# ITG-3200-v11.net
KiCad netlist of a schematic drawn in EAGLE
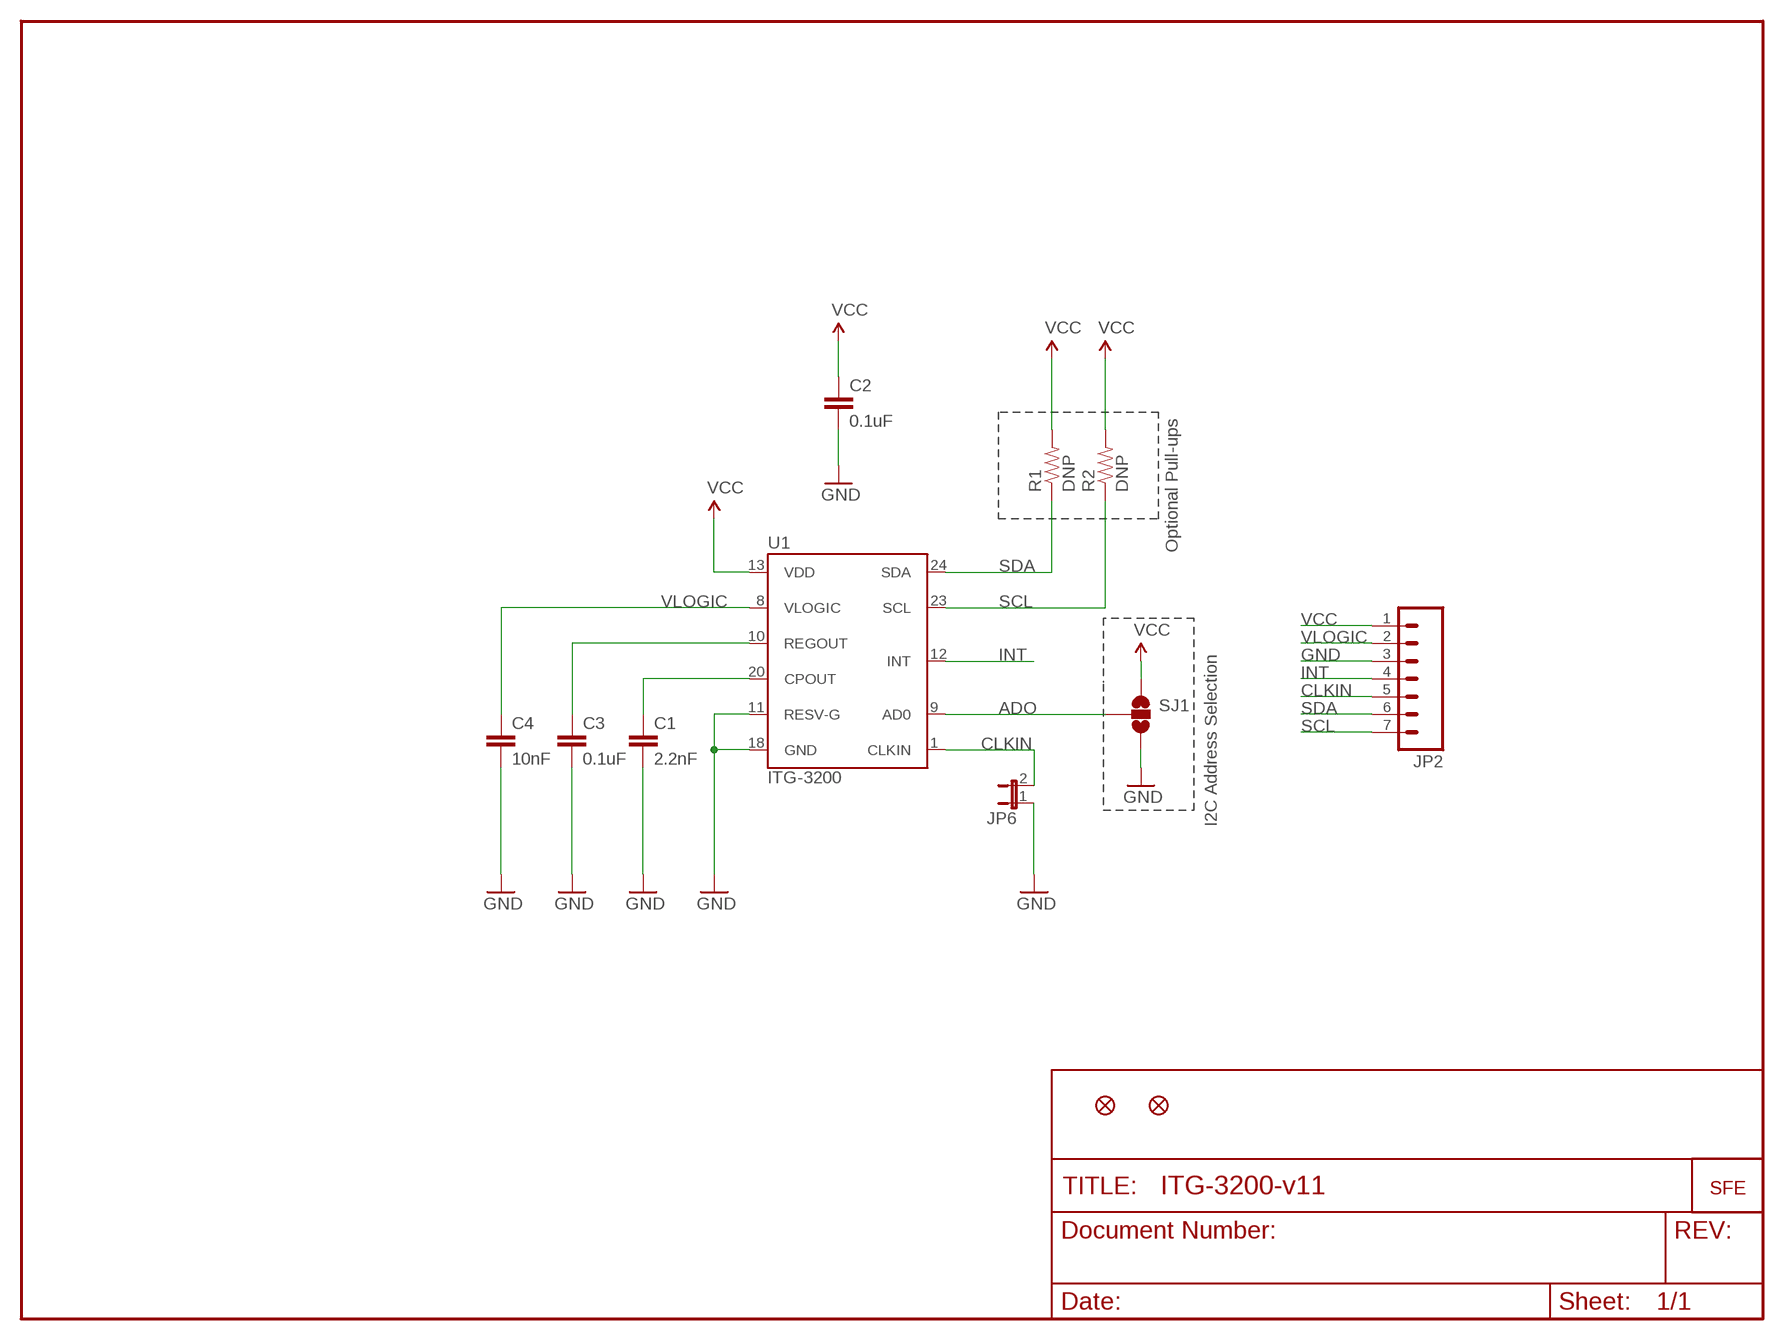
[diagram p0: schematic, sheet 1]

(export (version "E")
  (design (tool "Eeschema 10.0.6"))
  (components
    (comp (ref "C1")
      (value "2.2nF")
      (footprint "eagle-import:0603-CAP")
      (libsource (lib "eagle-import") (part "CAP0603-CAP"))
    )
    (comp (ref "C2")
      (value "0.1uF")
      (footprint "eagle-import:0603-CAP")
      (libsource (lib "eagle-import") (part "CAP0603-CAP"))
    )
    (comp (ref "C3")
      (value "0.1uF")
      (footprint "eagle-import:0603-CAP")
      (libsource (lib "eagle-import") (part "CAP0603-CAP"))
    )
    (comp (ref "C4")
      (value "10nF")
      (footprint "eagle-import:0603-CAP")
      (libsource (lib "eagle-import") (part "CAP0603-CAP"))
    )
    (comp (ref "JP1")
      (value "LOGO-SFESK")
      (footprint "eagle-import:SFE-LOGO-FLAME")
      (libsource (lib "eagle-import") (part "LOGO-SFESK"))
    )
    (comp (ref "JP2")
      (value "M07")
      (footprint "eagle-import:1X07")
      (libsource (lib "eagle-import") (part "M07"))
    )
    (comp (ref "JP3")
      (value "FIDUCIAL1X2")
      (footprint "eagle-import:FIDUCIAL-1X2")
      (libsource (lib "eagle-import") (part "FIDUCIAL1X2"))
    )
    (comp (ref "JP4")
      (value "FIDUCIAL1X2")
      (footprint "eagle-import:FIDUCIAL-1X2")
      (libsource (lib "eagle-import") (part "FIDUCIAL1X2"))
    )
    (comp (ref "JP6")
      (value "JUMPER-2SMD-NO")
      (footprint "eagle-import:SJ_2S-NO")
      (libsource (lib "eagle-import") (part "JUMPER-2SMD-NO"))
    )
    (comp (ref "R1")
      (value "DNP")
      (footprint "eagle-import:0603-RES")
      (libsource (lib "eagle-import") (part "RESISTOR0603-RES"))
    )
    (comp (ref "R2")
      (value "DNP")
      (footprint "eagle-import:0603-RES")
      (libsource (lib "eagle-import") (part "RESISTOR0603-RES"))
    )
    (comp (ref "SJ1")
      (value "SOLDERJUMPER_2WAYPASTE1&2")
      (footprint "eagle-import:SJ_3_PASTE1&2")
      (libsource (lib "eagle-import") (part "SOLDERJUMPER_2WAYPASTE1&2"))
    )
    (comp (ref "U1")
      (value "ITG-3200")
      (footprint "eagle-import:QFN-24")
      (libsource (lib "eagle-import") (part "ITG-3200"))
    )
  )
  (nets
    (net (code "1") (name "/ADO") (class "Default")
      (node (ref "SJ1") (pin "2") (pinfunction "2_2") (pintype "passive"))
      (node (ref "U1") (pin "9") (pinfunction "AD0_9") (pintype "bidirectional"))
    )
    (net (code "2") (name "/CLKIN") (class "Default")
      (node (ref "JP2") (pin "5") (pinfunction "5_5") (pintype "passive"))
      (node (ref "JP6") (pin "2") (pinfunction "2_2") (pintype "passive"))
      (node (ref "U1") (pin "1") (pinfunction "CLKIN_1") (pintype "bidirectional"))
    )
    (net (code "3") (name "/INT") (class "Default")
      (node (ref "JP2") (pin "4") (pinfunction "4_4") (pintype "passive"))
      (node (ref "U1") (pin "12") (pinfunction "INT_12") (pintype "bidirectional"))
    )
    (net (code "4") (name "/SCL") (class "Default")
      (node (ref "JP2") (pin "7") (pinfunction "7_7") (pintype "passive"))
      (node (ref "R2") (pin "1") (pinfunction "1_1") (pintype "passive"))
      (node (ref "U1") (pin "23") (pinfunction "SCL_23") (pintype "bidirectional"))
    )
    (net (code "5") (name "/SDA") (class "Default")
      (node (ref "JP2") (pin "6") (pinfunction "6_6") (pintype "passive"))
      (node (ref "R1") (pin "1") (pinfunction "1_1") (pintype "passive"))
      (node (ref "U1") (pin "24") (pinfunction "SDA_24") (pintype "bidirectional"))
    )
    (net (code "6") (name "/VLOGIC") (class "Default")
      (node (ref "C4") (pin "1") (pinfunction "1_1") (pintype "passive"))
      (node (ref "JP2") (pin "2") (pinfunction "2_2") (pintype "passive"))
      (node (ref "U1") (pin "8") (pinfunction "VLOGIC_8") (pintype "bidirectional"))
    )
    (net (code "7") (name "GND") (class "Default")
      (node (ref "C1") (pin "2") (pinfunction "2_2") (pintype "passive"))
      (node (ref "C2") (pin "2") (pinfunction "2_2") (pintype "passive"))
      (node (ref "C3") (pin "2") (pinfunction "2_2") (pintype "passive"))
      (node (ref "C4") (pin "2") (pinfunction "2_2") (pintype "passive"))
      (node (ref "JP2") (pin "3") (pinfunction "3_3") (pintype "passive"))
      (node (ref "JP6") (pin "1") (pinfunction "1_1") (pintype "passive"))
      (node (ref "SJ1") (pin "3") (pinfunction "3_3") (pintype "passive"))
      (node (ref "U1") (pin "11") (pinfunction "RESV-G_11") (pintype "bidirectional"))
      (node (ref "U1") (pin "18") (pinfunction "GND_18") (pintype "bidirectional"))
    )
    (net (code "8") (name "Net-(U1-CPOUT)") (class "Default")
      (node (ref "C1") (pin "1") (pinfunction "1_1") (pintype "passive"))
      (node (ref "U1") (pin "20") (pinfunction "CPOUT_20") (pintype "bidirectional"))
    )
    (net (code "9") (name "Net-(U1-REGOUT)") (class "Default")
      (node (ref "C3") (pin "1") (pinfunction "1_1") (pintype "passive"))
      (node (ref "U1") (pin "10") (pinfunction "REGOUT_10") (pintype "bidirectional"))
    )
    (net (code "10") (name "VCC") (class "Default")
      (node (ref "C2") (pin "1") (pinfunction "1_1") (pintype "passive"))
      (node (ref "JP2") (pin "1") (pinfunction "1_1") (pintype "passive"))
      (node (ref "R1") (pin "2") (pinfunction "2_2") (pintype "passive"))
      (node (ref "R2") (pin "2") (pinfunction "2_2") (pintype "passive"))
      (node (ref "SJ1") (pin "1") (pinfunction "1_1") (pintype "passive"))
      (node (ref "U1") (pin "13") (pinfunction "VDD_13") (pintype "bidirectional"))
    )
  )
)
